# design.net
KiCad netlist of a schematic drawn in Altium Designer
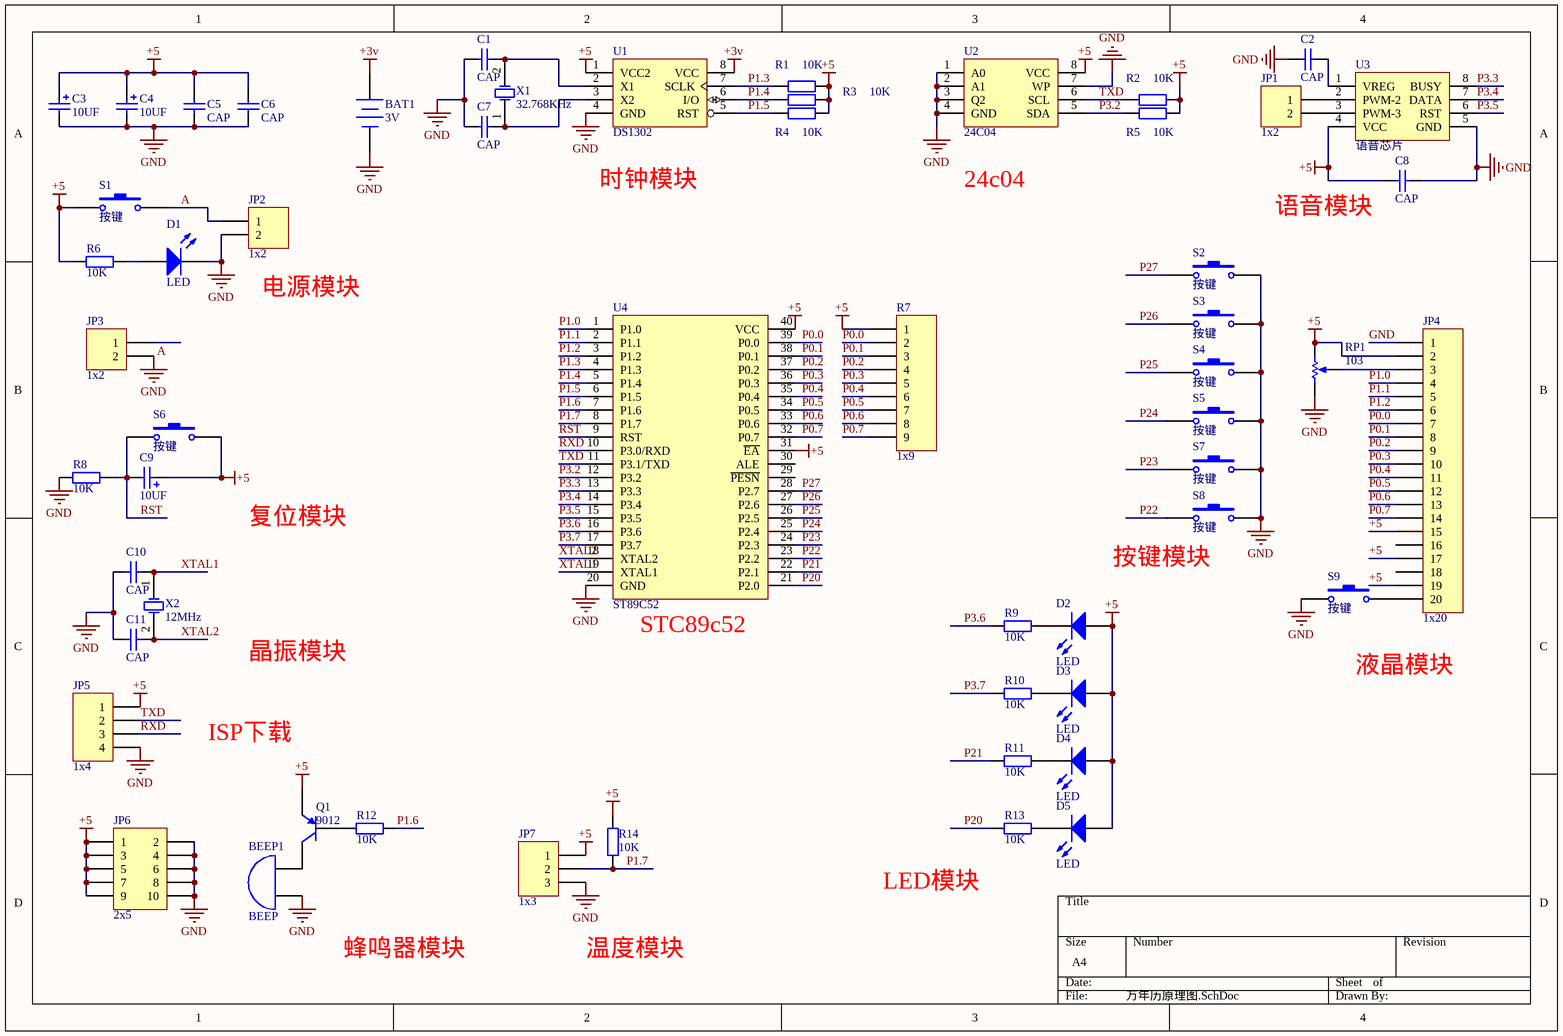
[diagram p0: 万年历原理图.SchDoc]

(export (version "E")
  (design (tool "Eeschema 10.0.6"))
  (components
    (comp (ref "BAT1") (value "3V") (footprint "CR3202") (libsource (lib "万年历原理图库") (part "电池")))
    (comp (ref "BEEP1") (value "BEEP") (footprint "BEEP") (libsource (lib "万年历原理图库") (part "蜂鸣器")))
    (comp (ref "C1") (value "CAP") (footprint "cap-cp") (libsource (lib "万年历原理图库") (part "瓷片电容")))
    (comp (ref "C2") (value "CAP") (footprint "cap-cp") (libsource (lib "万年历原理图库") (part "瓷片电容")))
    (comp (ref "C3") (value "10UF") (footprint "CAP-DJ") (libsource (lib "万年历原理图库") (part "电解电容")))
    (comp (ref "C4") (value "10UF") (footprint "CAP-DJ") (libsource (lib "万年历原理图库") (part "电解电容")))
    (comp (ref "C5") (value "CAP") (footprint "cap-cp") (libsource (lib "万年历原理图库") (part "瓷片电容")))
    (comp (ref "C6") (value "CAP") (footprint "cap-cp") (libsource (lib "万年历原理图库") (part "瓷片电容")))
    (comp (ref "C7") (value "CAP") (footprint "cap-cp") (libsource (lib "万年历原理图库") (part "瓷片电容")))
    (comp (ref "C8") (value "CAP") (footprint "cap-cp") (libsource (lib "万年历原理图库") (part "瓷片电容")))
    (comp (ref "C9") (value "10UF") (footprint "CAP-DJ") (libsource (lib "万年历原理图库") (part "电解电容")))
    (comp (ref "C10") (value "CAP") (footprint "cap-cp") (libsource (lib "万年历原理图库") (part "瓷片电容")))
    (comp (ref "C11") (value "CAP") (footprint "cap-cp") (libsource (lib "万年历原理图库") (part "瓷片电容")))
    (comp (ref "D1") (value "LED") (footprint "0805-led") (libsource (lib "万年历原理图库") (part "LED")))
    (comp (ref "D2") (value "LED") (footprint "0805-led") (libsource (lib "万年历原理图库") (part "LED")))
    (comp (ref "D3") (value "LED") (footprint "0805-led") (libsource (lib "万年历原理图库") (part "LED")))
    (comp (ref "D4") (value "LED") (footprint "0805-led") (libsource (lib "万年历原理图库") (part "LED")))
    (comp (ref "D5") (value "LED") (footprint "0805-led") (libsource (lib "万年历原理图库") (part "LED")))
    (comp (ref "JP1") (value "1x2") (footprint "PZ-2") (libsource (lib "") (part "1x2_1")))
    (comp (ref "JP2") (value "1x2") (footprint "dc-0005") (libsource (lib "万年历原理图库") (part "1x2")))
    (comp (ref "JP3") (value "1x2") (footprint "5.08DZ") (libsource (lib "") (part "1x2_1")))
    (comp (ref "JP4") (value "1x20") (footprint "PZ-20") (libsource (lib "万年历原理图库") (part "1x20")))
    (comp (ref "JP5") (value "1x4") (footprint "PZ-4") (libsource (lib "万年历原理图库") (part "1x4")))
    (comp (ref "JP6") (value "2x5") (footprint "PZ-2x5") (libsource (lib "万年历原理图库") (part "2x5")))
    (comp (ref "JP7") (value "1x3") (footprint "PZ-3") (libsource (lib "万年历原理图库") (part "1x3")))
    (comp (ref "Q1") (value "9012") (footprint "9012-TO-92") (libsource (lib "万年历原理图库") (part "PNP")))
    (comp (ref "R1") (value "10K") (footprint "0805-res") (libsource (lib "") (part "电阻_1")))
    (comp (ref "R2") (value "10K") (footprint "0805-res") (libsource (lib "") (part "电阻_1")))
    (comp (ref "R3") (value "10K") (footprint "0805-res") (libsource (lib "") (part "电阻_1")))
    (comp (ref "R4") (value "10K") (footprint "0805-res") (libsource (lib "") (part "电阻_1")))
    (comp (ref "R5") (value "10K") (footprint "0805-res") (libsource (lib "") (part "电阻_1")))
    (comp (ref "R6") (value "10K") (footprint "0805-res") (libsource (lib "") (part "电阻_1")))
    (comp (ref "R7") (value "1x9") (footprint "PZ-9") (libsource (lib "万年历原理图库") (part "1x9")))
    (comp (ref "R8") (value "10K") (footprint "0805-res") (libsource (lib "") (part "电阻_1")))
    (comp (ref "R9") (value "10K") (footprint "0805-res") (libsource (lib "万年历原理图库") (part "电阻")))
    (comp (ref "R10") (value "10K") (footprint "0805-res") (libsource (lib "万年历原理图库") (part "电阻")))
    (comp (ref "R11") (value "10K") (footprint "0805-res") (libsource (lib "万年历原理图库") (part "电阻")))
    (comp (ref "R12") (value "10K") (footprint "0805-res") (libsource (lib "万年历原理图库") (part "电阻")))
    (comp (ref "R13") (value "10K") (footprint "0805-res") (libsource (lib "万年历原理图库") (part "电阻")))
    (comp (ref "R14") (value "10K") (footprint "0805-res") (libsource (lib "") (part "电阻_2")))
    (comp (ref "RP1") (value "103") (footprint "VR") (libsource (lib "万年历原理图库") (part "可调电阻")))
    (comp (ref "S1") (value "按键") (footprint "key-6") (libsource (lib "万年历原理图库") (part "按键")))
    (comp (ref "S2") (value "按键") (footprint "KEY-4") (libsource (lib "万年历原理图库") (part "按键")))
    (comp (ref "S3") (value "按键") (footprint "KEY-4") (libsource (lib "万年历原理图库") (part "按键")))
    (comp (ref "S4") (value "按键") (footprint "KEY-4") (libsource (lib "万年历原理图库") (part "按键")))
    (comp (ref "S5") (value "按键") (footprint "KEY-4") (libsource (lib "万年历原理图库") (part "按键")))
    (comp (ref "S6") (value "按键") (footprint "KEY-4") (libsource (lib "万年历原理图库") (part "按键")))
    (comp (ref "S7") (value "按键") (footprint "KEY-4") (libsource (lib "万年历原理图库") (part "按键")))
    (comp (ref "S8") (value "按键") (footprint "KEY-4") (libsource (lib "万年历原理图库") (part "按键")))
    (comp (ref "S9") (value "按键") (footprint "key-6") (libsource (lib "万年历原理图库") (part "按键")))
    (comp (ref "U1") (value "DS1302") (footprint "DIP8") (libsource (lib "万年历原理图库") (part "DS1302")))
    (comp (ref "U2") (value "24C04") (footprint "DIP8") (libsource (lib "万年历原理图库") (part "24C04")))
    (comp (ref "U3") (value "语音芯片") (footprint "DIP8") (libsource (lib "万年历原理图库") (part "语音芯片")))
    (comp (ref "U4") (value "ST89C52") (footprint "DIP40") (libsource (lib "万年历原理图库") (part "STC89C52")))
    (comp (ref "X1") (value "32.768KHz") (footprint "32.768khz") (libsource (lib "万年历原理图库") (part "晶振")))
    (comp (ref "X2") (value "12MHz") (footprint "12mhz") (libsource (lib "万年历原理图库") (part "晶振")))
  )
  (nets
    (net (code "1") (name "+3v") (class "Default")
      (node (ref "BAT1") (pin "1") (pinfunction "+_1") (pintype "passive"))
      (node (ref "U1") (pin "8") (pinfunction "VCC_8") (pintype "passive"))
    )
    (net (code "2") (name "+5") (class "Default")
      (node (ref "C3") (pin "1") (pinfunction "1_1") (pintype "passive"))
      (node (ref "C4") (pin "1") (pinfunction "1_1") (pintype "passive"))
      (node (ref "C5") (pin "2") (pinfunction "2_2") (pintype "passive"))
      (node (ref "C6") (pin "2") (pinfunction "2_2") (pintype "passive"))
      (node (ref "C8") (pin "1") (pinfunction "1_1") (pintype "passive"))
      (node (ref "C9") (pin "1") (pinfunction "1_1") (pintype "passive"))
      (node (ref "D2") (pin "1") (pinfunction "A_1") (pintype "passive"))
      (node (ref "D3") (pin "1") (pinfunction "A_1") (pintype "passive"))
      (node (ref "D4") (pin "1") (pinfunction "A_1") (pintype "passive"))
      (node (ref "D5") (pin "1") (pinfunction "A_1") (pintype "passive"))
      (node (ref "JP4") (pin "15") (pinfunction "15_15") (pintype "passive"))
      (node (ref "JP4") (pin "17") (pinfunction "17_17") (pintype "passive"))
      (node (ref "JP4") (pin "19") (pinfunction "19_19") (pintype "passive"))
      (node (ref "JP4") (pin "2") (pinfunction "2_2") (pintype "passive"))
      (node (ref "JP5") (pin "1") (pinfunction "1_1") (pintype "passive"))
      (node (ref "JP6") (pin "1") (pinfunction "1_1") (pintype "passive"))
      (node (ref "JP6") (pin "3") (pinfunction "3_3") (pintype "passive"))
      (node (ref "JP6") (pin "5") (pinfunction "5_5") (pintype "passive"))
      (node (ref "JP6") (pin "7") (pinfunction "7_7") (pintype "passive"))
      (node (ref "JP6") (pin "9") (pinfunction "9_9") (pintype "passive"))
      (node (ref "JP7") (pin "1") (pinfunction "1_1") (pintype "passive"))
      (node (ref "Q1") (pin "1") (pinfunction "E_1") (pintype "passive"))
      (node (ref "R1") (pin "1") (pinfunction "1_1") (pintype "passive"))
      (node (ref "R14") (pin "2") (pinfunction "2_2") (pintype "passive"))
      (node (ref "R2") (pin "1") (pinfunction "1_1") (pintype "passive"))
      (node (ref "R3") (pin "1") (pinfunction "1_1") (pintype "passive"))
      (node (ref "R4") (pin "1") (pinfunction "1_1") (pintype "passive"))
      (node (ref "R5") (pin "1") (pinfunction "1_1") (pintype "passive"))
      (node (ref "R6") (pin "2") (pinfunction "2_2") (pintype "passive"))
      (node (ref "R7") (pin "1") (pinfunction "1_1") (pintype "passive"))
      (node (ref "RP1") (pin "3") (pinfunction "BOT_3") (pintype "passive"))
      (node (ref "S1") (pin "1") (pinfunction "1_1") (pintype "passive"))
      (node (ref "S6") (pin "2") (pinfunction "2_2") (pintype "passive"))
      (node (ref "U1") (pin "1") (pinfunction "VCC2_1") (pintype "passive"))
      (node (ref "U2") (pin "8") (pinfunction "VCC_8") (pintype "passive"))
      (node (ref "U3") (pin "4") (pinfunction "VCC_4") (pintype "passive"))
      (node (ref "U4") (pin "31") (pinfunction "~{EA}_31") (pintype "passive"))
      (node (ref "U4") (pin "40") (pinfunction "VCC_40") (pintype "passive"))
    )
    (net (code "3") (name "/A") (class "Default")
      (node (ref "JP2") (pin "1") (pinfunction "1_1") (pintype "passive"))
      (node (ref "JP3") (pin "1") (pinfunction "1_1") (pintype "passive"))
      (node (ref "S1") (pin "2") (pinfunction "2_2") (pintype "passive"))
    )
    (net (code "4") (name "/P0.0") (class "Default")
      (node (ref "JP4") (pin "7") (pinfunction "7_7") (pintype "passive"))
      (node (ref "R7") (pin "2") (pinfunction "2_2") (pintype "passive"))
      (node (ref "U4") (pin "39") (pinfunction "P0.0_39") (pintype "passive"))
    )
    (net (code "5") (name "/P0.1") (class "Default")
      (node (ref "JP4") (pin "8") (pinfunction "8_8") (pintype "passive"))
      (node (ref "R7") (pin "3") (pinfunction "3_3") (pintype "passive"))
      (node (ref "U4") (pin "38") (pinfunction "P0.1_38") (pintype "passive"))
    )
    (net (code "6") (name "/P0.2") (class "Default")
      (node (ref "JP4") (pin "9") (pinfunction "9_9") (pintype "passive"))
      (node (ref "R7") (pin "4") (pinfunction "4_4") (pintype "passive"))
      (node (ref "U4") (pin "37") (pinfunction "P0.2_37") (pintype "passive"))
    )
    (net (code "7") (name "/P0.3") (class "Default")
      (node (ref "JP4") (pin "10") (pinfunction "10_10") (pintype "passive"))
      (node (ref "R7") (pin "5") (pinfunction "5_5") (pintype "passive"))
      (node (ref "U4") (pin "36") (pinfunction "P0.3_36") (pintype "passive"))
    )
    (net (code "8") (name "/P0.4") (class "Default")
      (node (ref "JP4") (pin "11") (pinfunction "11_11") (pintype "passive"))
      (node (ref "R7") (pin "6") (pinfunction "6_6") (pintype "passive"))
      (node (ref "U4") (pin "35") (pinfunction "P0.4_35") (pintype "passive"))
    )
    (net (code "9") (name "/P0.5") (class "Default")
      (node (ref "JP4") (pin "12") (pinfunction "12_12") (pintype "passive"))
      (node (ref "R7") (pin "7") (pinfunction "7_7") (pintype "passive"))
      (node (ref "U4") (pin "34") (pinfunction "P0.5_34") (pintype "passive"))
    )
    (net (code "10") (name "/P0.6") (class "Default")
      (node (ref "JP4") (pin "13") (pinfunction "13_13") (pintype "passive"))
      (node (ref "R7") (pin "8") (pinfunction "8_8") (pintype "passive"))
      (node (ref "U4") (pin "33") (pinfunction "P0.6_33") (pintype "passive"))
    )
    (net (code "11") (name "/P0.7") (class "Default")
      (node (ref "JP4") (pin "14") (pinfunction "14_14") (pintype "passive"))
      (node (ref "R7") (pin "9") (pinfunction "9_9") (pintype "passive"))
      (node (ref "U4") (pin "32") (pinfunction "P0.7_32") (pintype "passive"))
    )
    (net (code "12") (name "/P1.0") (class "Default")
      (node (ref "JP4") (pin "4") (pinfunction "4_4") (pintype "passive"))
      (node (ref "U4") (pin "1") (pinfunction "P1.0_1") (pintype "passive"))
    )
    (net (code "13") (name "/P1.1") (class "Default")
      (node (ref "JP4") (pin "5") (pinfunction "5_5") (pintype "passive"))
      (node (ref "U4") (pin "2") (pinfunction "P1.1_2") (pintype "passive"))
    )
    (net (code "14") (name "/P1.2") (class "Default")
      (node (ref "JP4") (pin "6") (pinfunction "6_6") (pintype "passive"))
      (node (ref "U4") (pin "3") (pinfunction "P1.2_3") (pintype "passive"))
    )
    (net (code "15") (name "/P1.3") (class "Default")
      (node (ref "R1") (pin "2") (pinfunction "2_2") (pintype "passive"))
      (node (ref "U1") (pin "7") (pinfunction "SCLK_7") (pintype "passive"))
      (node (ref "U4") (pin "4") (pinfunction "P1.3_4") (pintype "passive"))
    )
    (net (code "16") (name "/P1.4") (class "Default")
      (node (ref "R3") (pin "2") (pinfunction "2_2") (pintype "passive"))
      (node (ref "U1") (pin "6") (pinfunction "I/O_6") (pintype "bidirectional"))
      (node (ref "U4") (pin "5") (pinfunction "P1.4_5") (pintype "passive"))
    )
    (net (code "17") (name "/P1.5") (class "Default")
      (node (ref "R4") (pin "2") (pinfunction "2_2") (pintype "passive"))
      (node (ref "U1") (pin "5") (pinfunction "RST_5") (pintype "passive"))
      (node (ref "U4") (pin "6") (pinfunction "P1.5_6") (pintype "passive"))
    )
    (net (code "18") (name "/P1.6") (class "Default")
      (node (ref "R12") (pin "2") (pinfunction "2_2") (pintype "passive"))
      (node (ref "U4") (pin "7") (pinfunction "P1.6_7") (pintype "passive"))
    )
    (net (code "19") (name "/P1.7") (class "Default")
      (node (ref "JP7") (pin "2") (pinfunction "2_2") (pintype "passive"))
      (node (ref "R14") (pin "1") (pinfunction "1_1") (pintype "passive"))
      (node (ref "U4") (pin "8") (pinfunction "P1.7_8") (pintype "passive"))
    )
    (net (code "20") (name "/P3.2") (class "Default")
      (node (ref "R5") (pin "2") (pinfunction "2_2") (pintype "passive"))
      (node (ref "U2") (pin "5") (pinfunction "SDA_5") (pintype "passive"))
      (node (ref "U4") (pin "12") (pinfunction "P3.2_12") (pintype "passive"))
    )
    (net (code "21") (name "/P3.3") (class "Default")
      (node (ref "U3") (pin "8") (pinfunction "BUSY_8") (pintype "passive"))
      (node (ref "U4") (pin "13") (pinfunction "P3.3_13") (pintype "passive"))
    )
    (net (code "22") (name "/P3.4") (class "Default")
      (node (ref "U3") (pin "7") (pinfunction "DATA_7") (pintype "passive"))
      (node (ref "U4") (pin "14") (pinfunction "P3.4_14") (pintype "passive"))
    )
    (net (code "23") (name "/P3.5") (class "Default")
      (node (ref "U3") (pin "6") (pinfunction "RST_6") (pintype "passive"))
      (node (ref "U4") (pin "15") (pinfunction "P3.5_15") (pintype "passive"))
    )
    (net (code "24") (name "/P3.6") (class "Default")
      (node (ref "R9") (pin "1") (pinfunction "1_1") (pintype "passive"))
      (node (ref "U4") (pin "16") (pinfunction "P3.6_16") (pintype "passive"))
    )
    (net (code "25") (name "/P3.7") (class "Default")
      (node (ref "R10") (pin "1") (pinfunction "1_1") (pintype "passive"))
      (node (ref "U4") (pin "17") (pinfunction "P3.7_17") (pintype "passive"))
    )
    (net (code "26") (name "/P20") (class "Default")
      (node (ref "R13") (pin "1") (pinfunction "1_1") (pintype "passive"))
      (node (ref "U4") (pin "21") (pinfunction "P2.0_21") (pintype "passive"))
    )
    (net (code "27") (name "/P21") (class "Default")
      (node (ref "R11") (pin "1") (pinfunction "1_1") (pintype "passive"))
      (node (ref "U4") (pin "22") (pinfunction "P2.1_22") (pintype "passive"))
    )
    (net (code "28") (name "/P22") (class "Default")
      (node (ref "S8") (pin "1") (pinfunction "1_1") (pintype "passive"))
      (node (ref "U4") (pin "23") (pinfunction "P2.2_23") (pintype "passive"))
    )
    (net (code "29") (name "/P23") (class "Default")
      (node (ref "S7") (pin "1") (pinfunction "1_1") (pintype "passive"))
      (node (ref "U4") (pin "24") (pinfunction "P2.3_24") (pintype "passive"))
    )
    (net (code "30") (name "/P24") (class "Default")
      (node (ref "S5") (pin "1") (pinfunction "1_1") (pintype "passive"))
      (node (ref "U4") (pin "25") (pinfunction "P2.4_25") (pintype "passive"))
    )
    (net (code "31") (name "/P25") (class "Default")
      (node (ref "S4") (pin "1") (pinfunction "1_1") (pintype "passive"))
      (node (ref "U4") (pin "26") (pinfunction "P2.5_26") (pintype "passive"))
    )
    (net (code "32") (name "/P26") (class "Default")
      (node (ref "S3") (pin "1") (pinfunction "1_1") (pintype "passive"))
      (node (ref "U4") (pin "27") (pinfunction "P2.6_27") (pintype "passive"))
    )
    (net (code "33") (name "/P27") (class "Default")
      (node (ref "S2") (pin "1") (pinfunction "1_1") (pintype "passive"))
      (node (ref "U4") (pin "28") (pinfunction "P2.7_28") (pintype "passive"))
    )
    (net (code "34") (name "/RST") (class "Default")
      (node (ref "C9") (pin "2") (pinfunction "2_2") (pintype "passive"))
      (node (ref "R8") (pin "1") (pinfunction "1_1") (pintype "passive"))
      (node (ref "S6") (pin "1") (pinfunction "1_1") (pintype "passive"))
      (node (ref "U4") (pin "9") (pinfunction "RST_9") (pintype "passive"))
    )
    (net (code "35") (name "/RXD") (class "Default")
      (node (ref "JP5") (pin "3") (pinfunction "3_3") (pintype "passive"))
      (node (ref "U4") (pin "10") (pinfunction "P3.0/RXD_10") (pintype "passive"))
    )
    (net (code "36") (name "/TXD") (class "Default")
      (node (ref "JP5") (pin "2") (pinfunction "2_2") (pintype "passive"))
      (node (ref "R2") (pin "2") (pinfunction "2_2") (pintype "passive"))
      (node (ref "U2") (pin "6") (pinfunction "SCL_6") (pintype "passive"))
      (node (ref "U4") (pin "11") (pinfunction "P3.1/TXD_11") (pintype "passive"))
    )
    (net (code "37") (name "/XTAL1") (class "Default")
      (node (ref "C10") (pin "2") (pinfunction "2_2") (pintype "passive"))
      (node (ref "U4") (pin "19") (pinfunction "XTAL1_19") (pintype "passive"))
      (node (ref "X2") (pin "1") (pinfunction "OSC1_1") (pintype "passive"))
    )
    (net (code "38") (name "/XTAL2") (class "Default")
      (node (ref "C11") (pin "2") (pinfunction "2_2") (pintype "passive"))
      (node (ref "U4") (pin "18") (pinfunction "XTAL2_18") (pintype "passive"))
      (node (ref "X2") (pin "2") (pinfunction "OSC2_2") (pintype "passive"))
    )
    (net (code "39") (name "GND") (class "Default")
      (node (ref "BAT1") (pin "2") (pinfunction "-_2") (pintype "passive"))
      (node (ref "BEEP1") (pin "2") (pinfunction "B_2") (pintype "passive"))
      (node (ref "C1") (pin "1") (pinfunction "1_1") (pintype "passive"))
      (node (ref "C10") (pin "1") (pinfunction "1_1") (pintype "passive"))
      (node (ref "C11") (pin "1") (pinfunction "1_1") (pintype "passive"))
      (node (ref "C2") (pin "2") (pinfunction "2_2") (pintype "passive"))
      (node (ref "C3") (pin "2") (pinfunction "2_2") (pintype "passive"))
      (node (ref "C4") (pin "2") (pinfunction "2_2") (pintype "passive"))
      (node (ref "C5") (pin "1") (pinfunction "1_1") (pintype "passive"))
      (node (ref "C6") (pin "1") (pinfunction "1_1") (pintype "passive"))
      (node (ref "C7") (pin "1") (pinfunction "1_1") (pintype "passive"))
      (node (ref "C8") (pin "2") (pinfunction "2_2") (pintype "passive"))
      (node (ref "D1") (pin "2") (pinfunction "K_2") (pintype "passive"))
      (node (ref "JP2") (pin "2") (pinfunction "2_2") (pintype "passive"))
      (node (ref "JP3") (pin "2") (pinfunction "2_2") (pintype "passive"))
      (node (ref "JP4") (pin "1") (pinfunction "1_1") (pintype "passive"))
      (node (ref "JP5") (pin "4") (pinfunction "4_4") (pintype "passive"))
      (node (ref "JP6") (pin "10") (pinfunction "10_10") (pintype "passive"))
      (node (ref "JP6") (pin "2") (pinfunction "2_2") (pintype "passive"))
      (node (ref "JP6") (pin "4") (pinfunction "4_4") (pintype "passive"))
      (node (ref "JP6") (pin "6") (pinfunction "6_6") (pintype "passive"))
      (node (ref "JP6") (pin "8") (pinfunction "8_8") (pintype "passive"))
      (node (ref "JP7") (pin "3") (pinfunction "3_3") (pintype "passive"))
      (node (ref "R8") (pin "2") (pinfunction "2_2") (pintype "passive"))
      (node (ref "RP1") (pin "1") (pinfunction "TOP_1") (pintype "passive"))
      (node (ref "S2") (pin "2") (pinfunction "2_2") (pintype "passive"))
      (node (ref "S3") (pin "2") (pinfunction "2_2") (pintype "passive"))
      (node (ref "S4") (pin "2") (pinfunction "2_2") (pintype "passive"))
      (node (ref "S5") (pin "2") (pinfunction "2_2") (pintype "passive"))
      (node (ref "S7") (pin "2") (pinfunction "2_2") (pintype "passive"))
      (node (ref "S8") (pin "2") (pinfunction "2_2") (pintype "passive"))
      (node (ref "S9") (pin "1") (pinfunction "1_1") (pintype "passive"))
      (node (ref "U1") (pin "4") (pinfunction "GND_4") (pintype "passive"))
      (node (ref "U2") (pin "1") (pinfunction "A0_1") (pintype "passive"))
      (node (ref "U2") (pin "2") (pinfunction "A1_2") (pintype "passive"))
      (node (ref "U2") (pin "3") (pinfunction "Q2_3") (pintype "passive"))
      (node (ref "U2") (pin "4") (pinfunction "GND_4") (pintype "passive"))
      (node (ref "U2") (pin "7") (pinfunction "WP_7") (pintype "passive"))
      (node (ref "U3") (pin "5") (pinfunction "GND_5") (pintype "passive"))
      (node (ref "U4") (pin "20") (pinfunction "GND_20") (pintype "passive"))
    )
    (net (code "40") (name "Net-(BEEP1-A)") (class "Default")
      (node (ref "BEEP1") (pin "1") (pinfunction "A_1") (pintype "passive"))
      (node (ref "Q1") (pin "3") (pinfunction "C_3") (pintype "passive"))
    )
    (net (code "41") (name "Net-(D1-A)") (class "Default")
      (node (ref "D1") (pin "1") (pinfunction "A_1") (pintype "passive"))
      (node (ref "R6") (pin "1") (pinfunction "1_1") (pintype "passive"))
    )
    (net (code "42") (name "Net-(D2-K)") (class "Default")
      (node (ref "D2") (pin "2") (pinfunction "K_2") (pintype "passive"))
      (node (ref "R9") (pin "2") (pinfunction "2_2") (pintype "passive"))
    )
    (net (code "43") (name "Net-(D3-K)") (class "Default")
      (node (ref "D3") (pin "2") (pinfunction "K_2") (pintype "passive"))
      (node (ref "R10") (pin "2") (pinfunction "2_2") (pintype "passive"))
    )
    (net (code "44") (name "Net-(D4-K)") (class "Default")
      (node (ref "D4") (pin "2") (pinfunction "K_2") (pintype "passive"))
      (node (ref "R11") (pin "2") (pinfunction "2_2") (pintype "passive"))
    )
    (net (code "45") (name "Net-(D5-K)") (class "Default")
      (node (ref "D5") (pin "2") (pinfunction "K_2") (pintype "passive"))
      (node (ref "R13") (pin "2") (pinfunction "2_2") (pintype "passive"))
    )
    (net (code "46") (name "Net-(JP4-Pad20)") (class "Default")
      (node (ref "JP4") (pin "20") (pinfunction "20_20") (pintype "passive"))
      (node (ref "S9") (pin "2") (pinfunction "2_2") (pintype "passive"))
    )
    (net (code "47") (name "Net-(Q1-B)") (class "Default")
      (node (ref "Q1") (pin "2") (pinfunction "B_2") (pintype "passive"))
      (node (ref "R12") (pin "1") (pinfunction "1_1") (pintype "passive"))
    )
    (net (code "48") (name "Net-(RP1-TAP)") (class "Default")
      (node (ref "JP4") (pin "3") (pinfunction "3_3") (pintype "passive"))
      (node (ref "RP1") (pin "2") (pinfunction "TAP_2") (pintype "passive"))
    )
    (net (code "49") (name "Net-(U1-X1)") (class "Default")
      (node (ref "C1") (pin "2") (pinfunction "2_2") (pintype "passive"))
      (node (ref "U1") (pin "2") (pinfunction "X1_2") (pintype "passive"))
      (node (ref "X1") (pin "2") (pinfunction "OSC2_2") (pintype "passive"))
    )
    (net (code "50") (name "Net-(U1-X2)") (class "Default")
      (node (ref "C7") (pin "2") (pinfunction "2_2") (pintype "passive"))
      (node (ref "U1") (pin "3") (pinfunction "X2_3") (pintype "passive"))
      (node (ref "X1") (pin "1") (pinfunction "OSC1_1") (pintype "passive"))
    )
    (net (code "51") (name "Net-(U3-PWM-2)") (class "Default")
      (node (ref "JP1") (pin "1") (pinfunction "1_1") (pintype "passive"))
      (node (ref "U3") (pin "2") (pinfunction "PWM-2_2") (pintype "passive"))
    )
    (net (code "52") (name "Net-(U3-PWM-3)") (class "Default")
      (node (ref "JP1") (pin "2") (pinfunction "2_2") (pintype "passive"))
      (node (ref "U3") (pin "3") (pinfunction "PWM-3_3") (pintype "passive"))
    )
    (net (code "53") (name "Net-(U3-VREG)") (class "Default")
      (node (ref "C2") (pin "1") (pinfunction "1_1") (pintype "passive"))
      (node (ref "U3") (pin "1") (pinfunction "VREG_1") (pintype "passive"))
    )
    (net (code "54") (name "unconnected-(JP4-Pad16)") (class "Default")
      (node (ref "JP4") (pin "16") (pinfunction "16_16") (pintype "passive"))
    )
    (net (code "55") (name "unconnected-(JP4-Pad18)") (class "Default")
      (node (ref "JP4") (pin "18") (pinfunction "18_18") (pintype "passive"))
    )
    (net (code "56") (name "unconnected-(U4-ALE-Pad30)") (class "Default")
      (node (ref "U4") (pin "30") (pinfunction "ALE_30") (pintype "passive"))
    )
    (net (code "57") (name "unconnected-(U4-~{PESN}-Pad29)") (class "Default")
      (node (ref "U4") (pin "29") (pinfunction "~{PESN}_29") (pintype "passive"))
    )
  )
)
